# power_supply.net
KiCad netlist of a schematic drawn in EAGLE
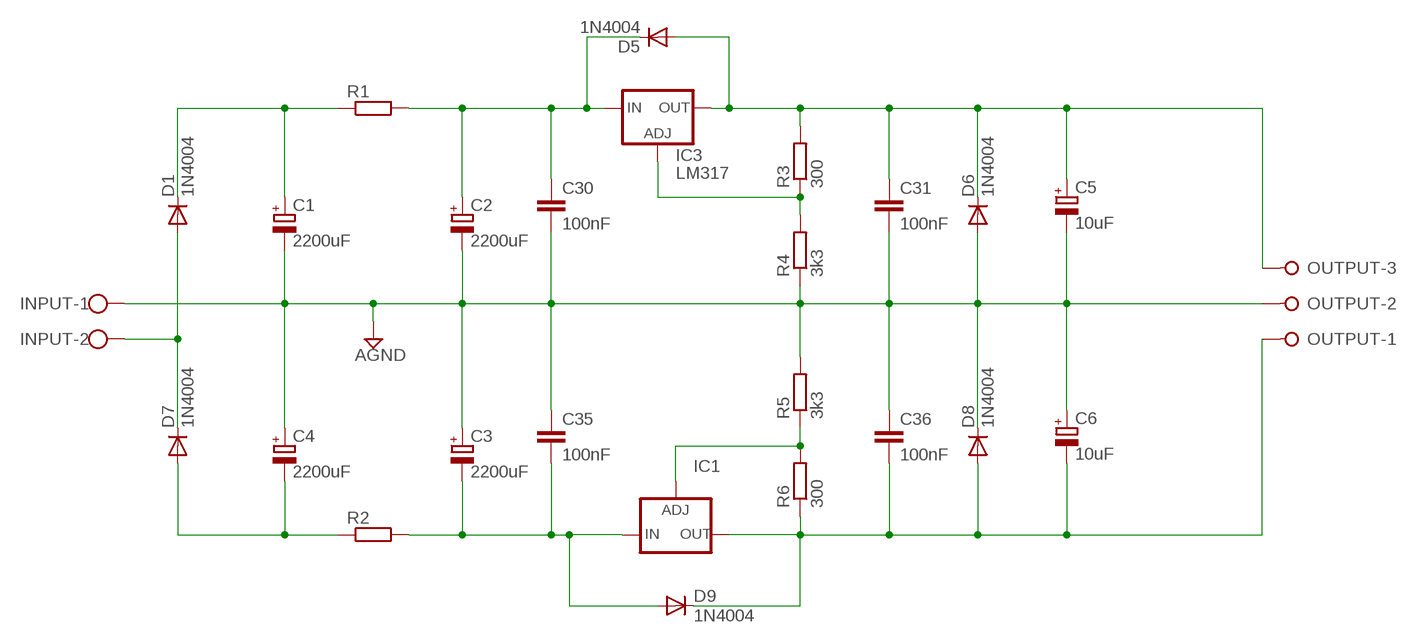
[diagram p0: schematic, sheet 1]

(export (version "E")
  (design (tool "Eeschema 10.0.6"))
  (components
    (comp (ref "C1")
      (value "2200uF")
      (footprint "eagle-import:E7,5-16")
      (libsource (lib "eagle-import") (part "CPOL-EUE7.5-16"))
    )
    (comp (ref "C2")
      (value "2200uF")
      (footprint "eagle-import:E7,5-16")
      (libsource (lib "eagle-import") (part "CPOL-EUE7.5-16"))
    )
    (comp (ref "C3")
      (value "2200uF")
      (footprint "eagle-import:E7,5-16")
      (libsource (lib "eagle-import") (part "CPOL-EUE7.5-16"))
    )
    (comp (ref "C4")
      (value "2200uF")
      (footprint "eagle-import:E7,5-16")
      (libsource (lib "eagle-import") (part "CPOL-EUE7.5-16"))
    )
    (comp (ref "C5")
      (value "10uF")
      (footprint "eagle-import:E2,5-5")
      (libsource (lib "eagle-import") (part "CPOL-EUE2.5-5"))
    )
    (comp (ref "C6")
      (value "10uF")
      (footprint "eagle-import:E2,5-5")
      (libsource (lib "eagle-import") (part "CPOL-EUE2.5-5"))
    )
    (comp (ref "C30")
      (value "100nF")
      (footprint "eagle-import:C050-025X075")
      (libsource (lib "eagle-import") (part "C-EU050-025X075"))
    )
    (comp (ref "C31")
      (value "100nF")
      (footprint "eagle-import:C050-025X075")
      (libsource (lib "eagle-import") (part "C-EU050-025X075"))
    )
    (comp (ref "C35")
      (value "100nF")
      (footprint "eagle-import:C050-025X075")
      (libsource (lib "eagle-import") (part "C-EU050-025X075"))
    )
    (comp (ref "C36")
      (value "100nF")
      (footprint "eagle-import:C050-025X075")
      (libsource (lib "eagle-import") (part "C-EU050-025X075"))
    )
    (comp (ref "D1")
      (value "1N4004")
      (footprint "eagle-import:DO41-10")
      (libsource (lib "eagle-import") (part "1N4004"))
    )
    (comp (ref "D5")
      (value "1N4004")
      (footprint "eagle-import:DO41-10")
      (libsource (lib "eagle-import") (part "1N4004"))
    )
    (comp (ref "D6")
      (value "1N4004")
      (footprint "eagle-import:DO41-10")
      (libsource (lib "eagle-import") (part "1N4004"))
    )
    (comp (ref "D7")
      (value "1N4004")
      (footprint "eagle-import:DO41-10")
      (libsource (lib "eagle-import") (part "1N4004"))
    )
    (comp (ref "D8")
      (value "1N4004")
      (footprint "eagle-import:DO41-10")
      (libsource (lib "eagle-import") (part "1N4004"))
    )
    (comp (ref "D9")
      (value "1N4004")
      (footprint "eagle-import:DO41-10")
      (libsource (lib "eagle-import") (part "1N4004"))
    )
    (comp (ref "IC1")
      (value "LM337TS")
      (footprint "eagle-import:337TS")
      (libsource (lib "eagle-import") (part "LM337TS"))
    )
    (comp (ref "IC3")
      (value "LM317")
      (footprint "eagle-import:317TS")
      (libsource (lib "eagle-import") (part "LM317TS"))
    )
    (comp (ref "INPUT")
      (value "W237-102")
      (footprint "eagle-import:W237-102")
      (fields (field (name "MPN") "237-102"))
      (libsource (lib "eagle-import") (part "W237-102"))
    )
    (comp (ref "OUTPUT")
      (value "W237-3E")
      (footprint "eagle-import:W237-3E")
      (libsource (lib "eagle-import") (part "W237-3E"))
    )
    (comp (ref "R1")
      (value "R-EU_0207/10")
      (footprint "eagle-import:0207_10")
      (libsource (lib "eagle-import") (part "R-EU_0207/10"))
    )
    (comp (ref "R2")
      (value "R-EU_0207/10")
      (footprint "eagle-import:0207_10")
      (libsource (lib "eagle-import") (part "R-EU_0207/10"))
    )
    (comp (ref "R3")
      (value "300")
      (footprint "eagle-import:0207_7")
      (libsource (lib "eagle-import") (part "R-EU_0207/7"))
    )
    (comp (ref "R4")
      (value "3k3")
      (footprint "eagle-import:0207_7")
      (libsource (lib "eagle-import") (part "R-EU_0207/7"))
    )
    (comp (ref "R5")
      (value "3k3")
      (footprint "eagle-import:0207_7")
      (libsource (lib "eagle-import") (part "R-EU_0207/7"))
    )
    (comp (ref "R6")
      (value "300")
      (footprint "eagle-import:0207_7")
      (libsource (lib "eagle-import") (part "R-EU_0207/7"))
    )
  )
  (nets
    (net (code "1") (name "AGND") (class "Default")
      (node (ref "C1") (pin "-") (pinfunction "-_-") (pintype "passive"))
      (node (ref "C2") (pin "-") (pinfunction "-_-") (pintype "passive"))
      (node (ref "C3") (pin "+") (pinfunction "+_+") (pintype "passive"))
      (node (ref "C30") (pin "2") (pinfunction "2_2") (pintype "passive"))
      (node (ref "C31") (pin "2") (pinfunction "2_2") (pintype "passive"))
      (node (ref "C35") (pin "1") (pinfunction "1_1") (pintype "passive"))
      (node (ref "C36") (pin "1") (pinfunction "1_1") (pintype "passive"))
      (node (ref "C4") (pin "+") (pinfunction "+_+") (pintype "passive"))
      (node (ref "C5") (pin "-") (pinfunction "-_-") (pintype "passive"))
      (node (ref "C6") (pin "+") (pinfunction "+_+") (pintype "passive"))
      (node (ref "D6") (pin "A") (pinfunction "A_A") (pintype "passive"))
      (node (ref "D8") (pin "C") (pinfunction "C_C") (pintype "passive"))
      (node (ref "INPUT") (pin "1") (pinfunction "KL_1") (pintype "passive"))
      (node (ref "OUTPUT") (pin "2") (pinfunction "KL_2") (pintype "passive"))
      (node (ref "R4") (pin "1") (pinfunction "1_1") (pintype "passive"))
      (node (ref "R5") (pin "2") (pinfunction "2_2") (pintype "passive"))
    )
    (net (code "2") (name "Net-(C1-Pad+)") (class "Default")
      (node (ref "C1") (pin "+") (pinfunction "+_+") (pintype "passive"))
      (node (ref "D1") (pin "C") (pinfunction "C_C") (pintype "passive"))
      (node (ref "R1") (pin "1") (pinfunction "1_1") (pintype "passive"))
    )
    (net (code "3") (name "Net-(C4-Pad-)") (class "Default")
      (node (ref "C4") (pin "-") (pinfunction "-_-") (pintype "passive"))
      (node (ref "D7") (pin "A") (pinfunction "A_A") (pintype "passive"))
      (node (ref "R2") (pin "1") (pinfunction "1_1") (pintype "passive"))
    )
    (net (code "4") (name "Net-(IC1-ADJ)") (class "Default")
      (node (ref "IC1") (pin "1") (pinfunction "ADJ_1") (pintype "input"))
      (node (ref "R5") (pin "1") (pinfunction "1_1") (pintype "passive"))
      (node (ref "R6") (pin "2") (pinfunction "2_2") (pintype "passive"))
    )
    (net (code "5") (name "Net-(IC1-IN)") (class "Default")
      (node (ref "C3") (pin "-") (pinfunction "-_-") (pintype "passive"))
      (node (ref "C35") (pin "2") (pinfunction "2_2") (pintype "passive"))
      (node (ref "D9") (pin "A") (pinfunction "A_A") (pintype "passive"))
      (node (ref "IC1") (pin "2") (pinfunction "IN_2") (pintype "input"))
      (node (ref "R2") (pin "2") (pinfunction "2_2") (pintype "passive"))
    )
    (net (code "6") (name "Net-(IC1-OUT)") (class "Default")
      (node (ref "C36") (pin "2") (pinfunction "2_2") (pintype "passive"))
      (node (ref "C6") (pin "-") (pinfunction "-_-") (pintype "passive"))
      (node (ref "D8") (pin "A") (pinfunction "A_A") (pintype "passive"))
      (node (ref "D9") (pin "C") (pinfunction "C_C") (pintype "passive"))
      (node (ref "IC1") (pin "3") (pinfunction "OUT_3") (pintype "passive"))
      (node (ref "OUTPUT") (pin "1") (pinfunction "KL_1") (pintype "passive"))
      (node (ref "R6") (pin "1") (pinfunction "1_1") (pintype "passive"))
    )
    (net (code "7") (name "Net-(IC3-ADJ)") (class "Default")
      (node (ref "IC3") (pin "1") (pinfunction "ADJ_1") (pintype "input"))
      (node (ref "R3") (pin "1") (pinfunction "1_1") (pintype "passive"))
      (node (ref "R4") (pin "2") (pinfunction "2_2") (pintype "passive"))
    )
    (net (code "8") (name "Net-(IC3-IN)") (class "Default")
      (node (ref "C2") (pin "+") (pinfunction "+_+") (pintype "passive"))
      (node (ref "C30") (pin "1") (pinfunction "1_1") (pintype "passive"))
      (node (ref "D5") (pin "C") (pinfunction "C_C") (pintype "passive"))
      (node (ref "IC3") (pin "3") (pinfunction "IN_3") (pintype "input"))
      (node (ref "R1") (pin "2") (pinfunction "2_2") (pintype "passive"))
    )
    (net (code "9") (name "Net-(IC3-OUT)") (class "Default")
      (node (ref "C31") (pin "1") (pinfunction "1_1") (pintype "passive"))
      (node (ref "C5") (pin "+") (pinfunction "+_+") (pintype "passive"))
      (node (ref "D5") (pin "A") (pinfunction "A_A") (pintype "passive"))
      (node (ref "D6") (pin "C") (pinfunction "C_C") (pintype "passive"))
      (node (ref "IC3") (pin "2") (pinfunction "OUT_2") (pintype "passive"))
      (node (ref "OUTPUT") (pin "3") (pinfunction "KL_3") (pintype "passive"))
      (node (ref "R3") (pin "2") (pinfunction "2_2") (pintype "passive"))
    )
    (net (code "10") (name "Net-(INPUTB-KL)") (class "Default")
      (node (ref "D1") (pin "A") (pinfunction "A_A") (pintype "passive"))
      (node (ref "D7") (pin "C") (pinfunction "C_C") (pintype "passive"))
      (node (ref "INPUT") (pin "2") (pinfunction "KL_2") (pintype "passive"))
    )
  )
)
